# Main-v5_0.net
KiCad netlist of a schematic drawn in EAGLE
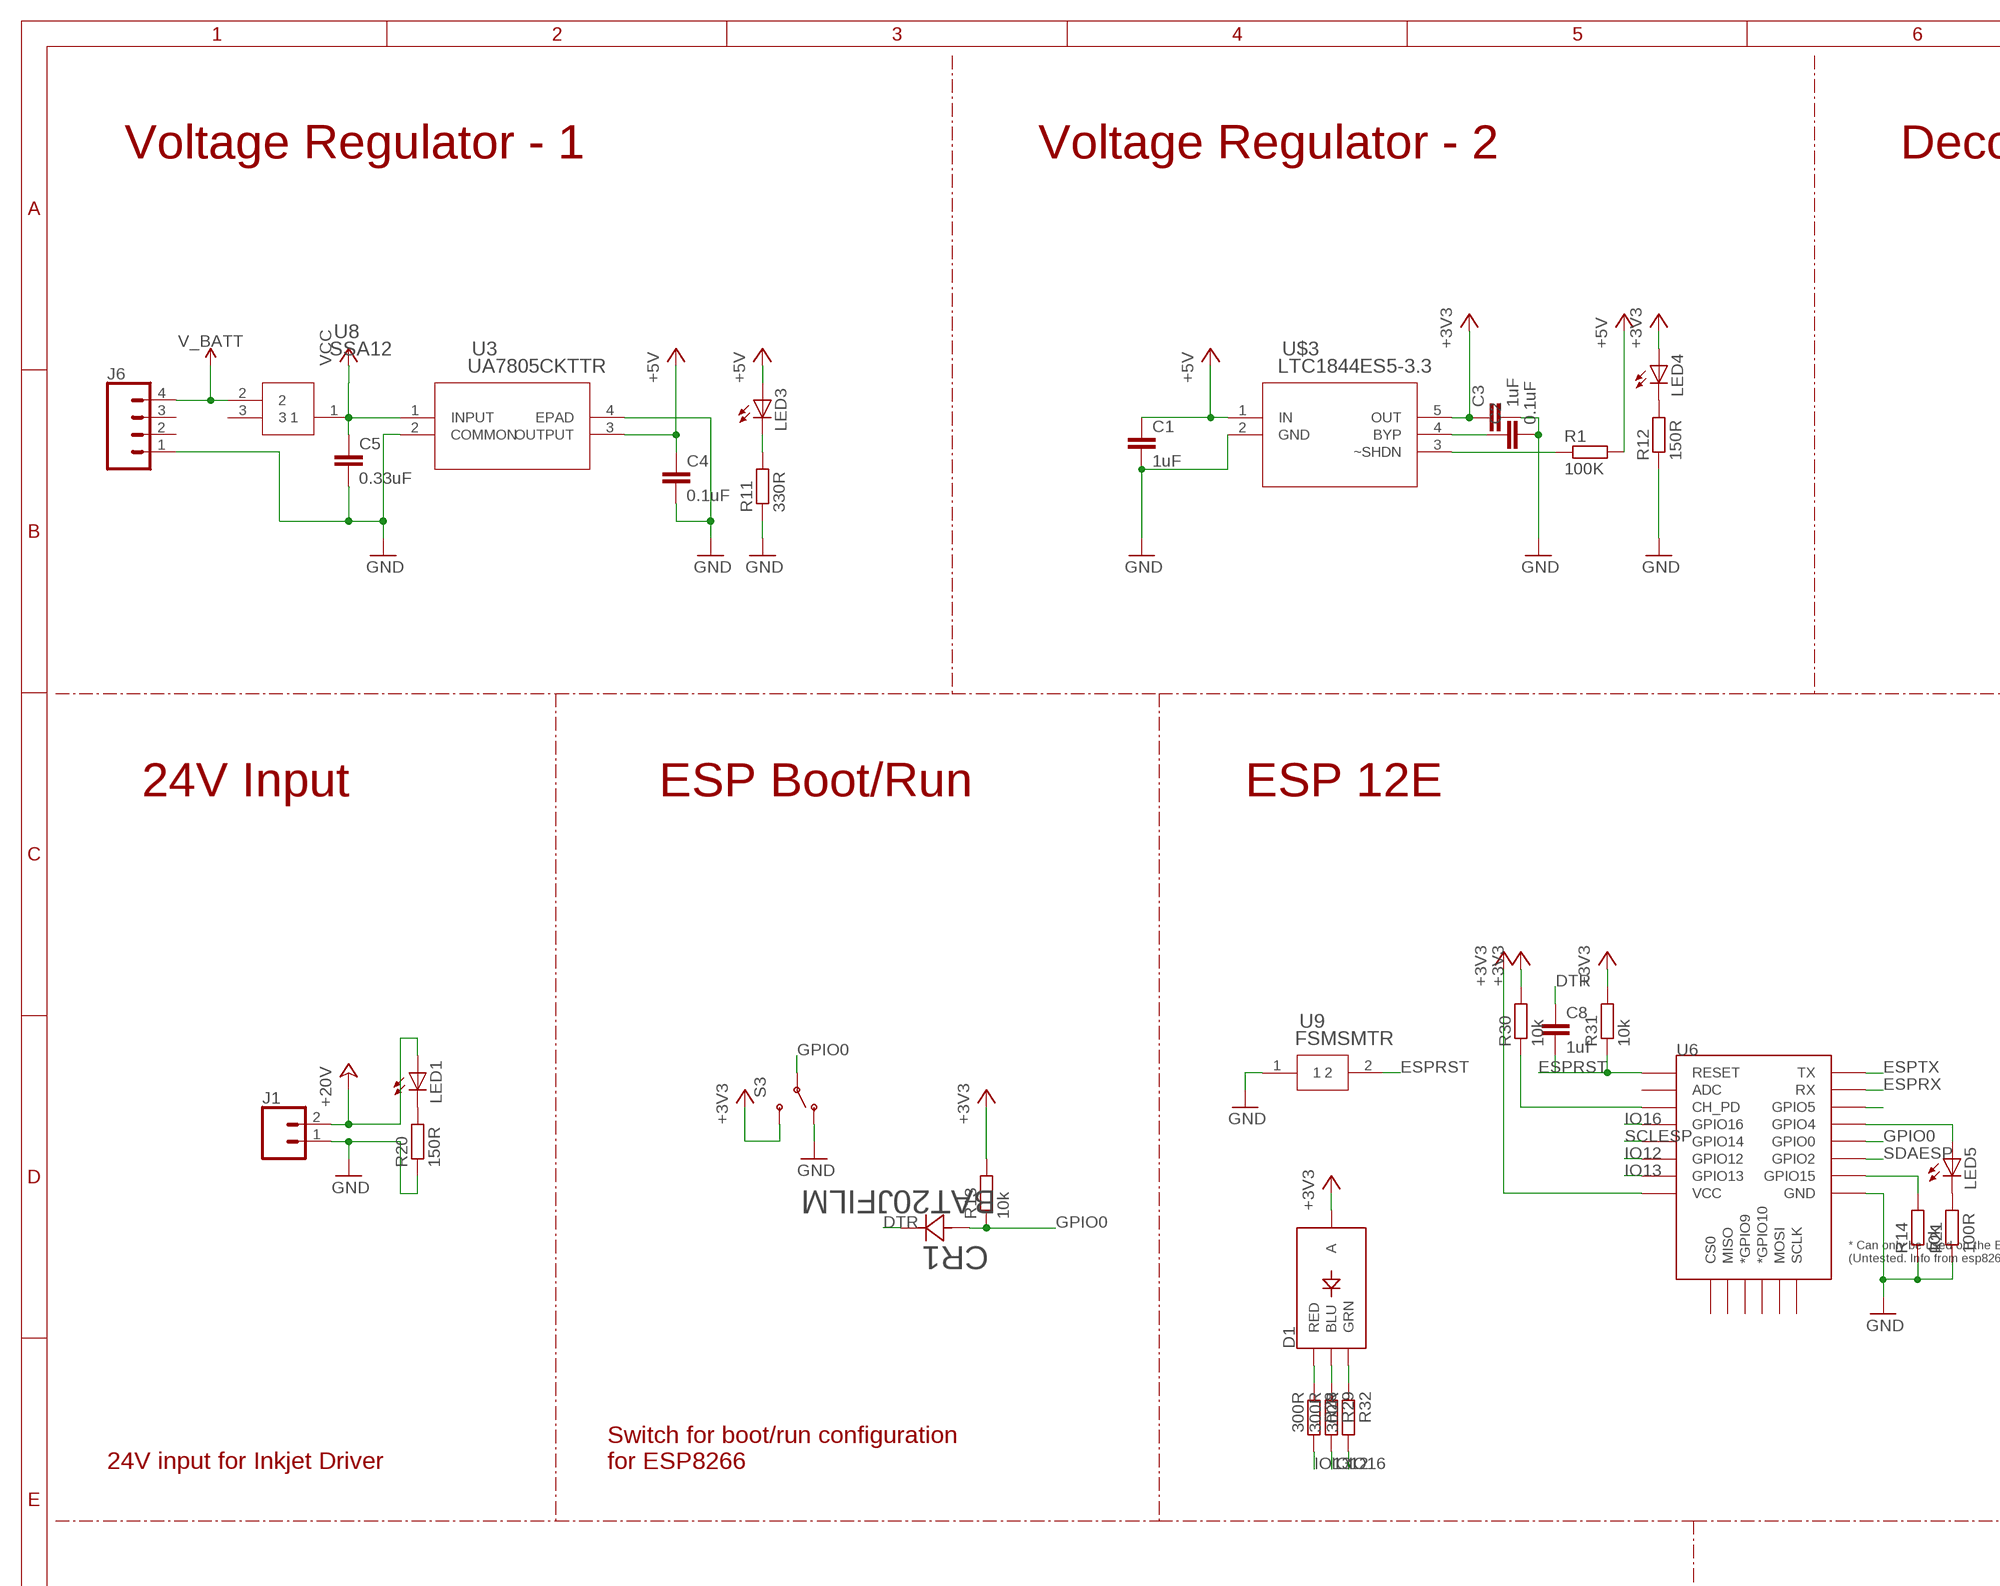
[diagram p0: schematic, sheet 1, part 1 of 3]
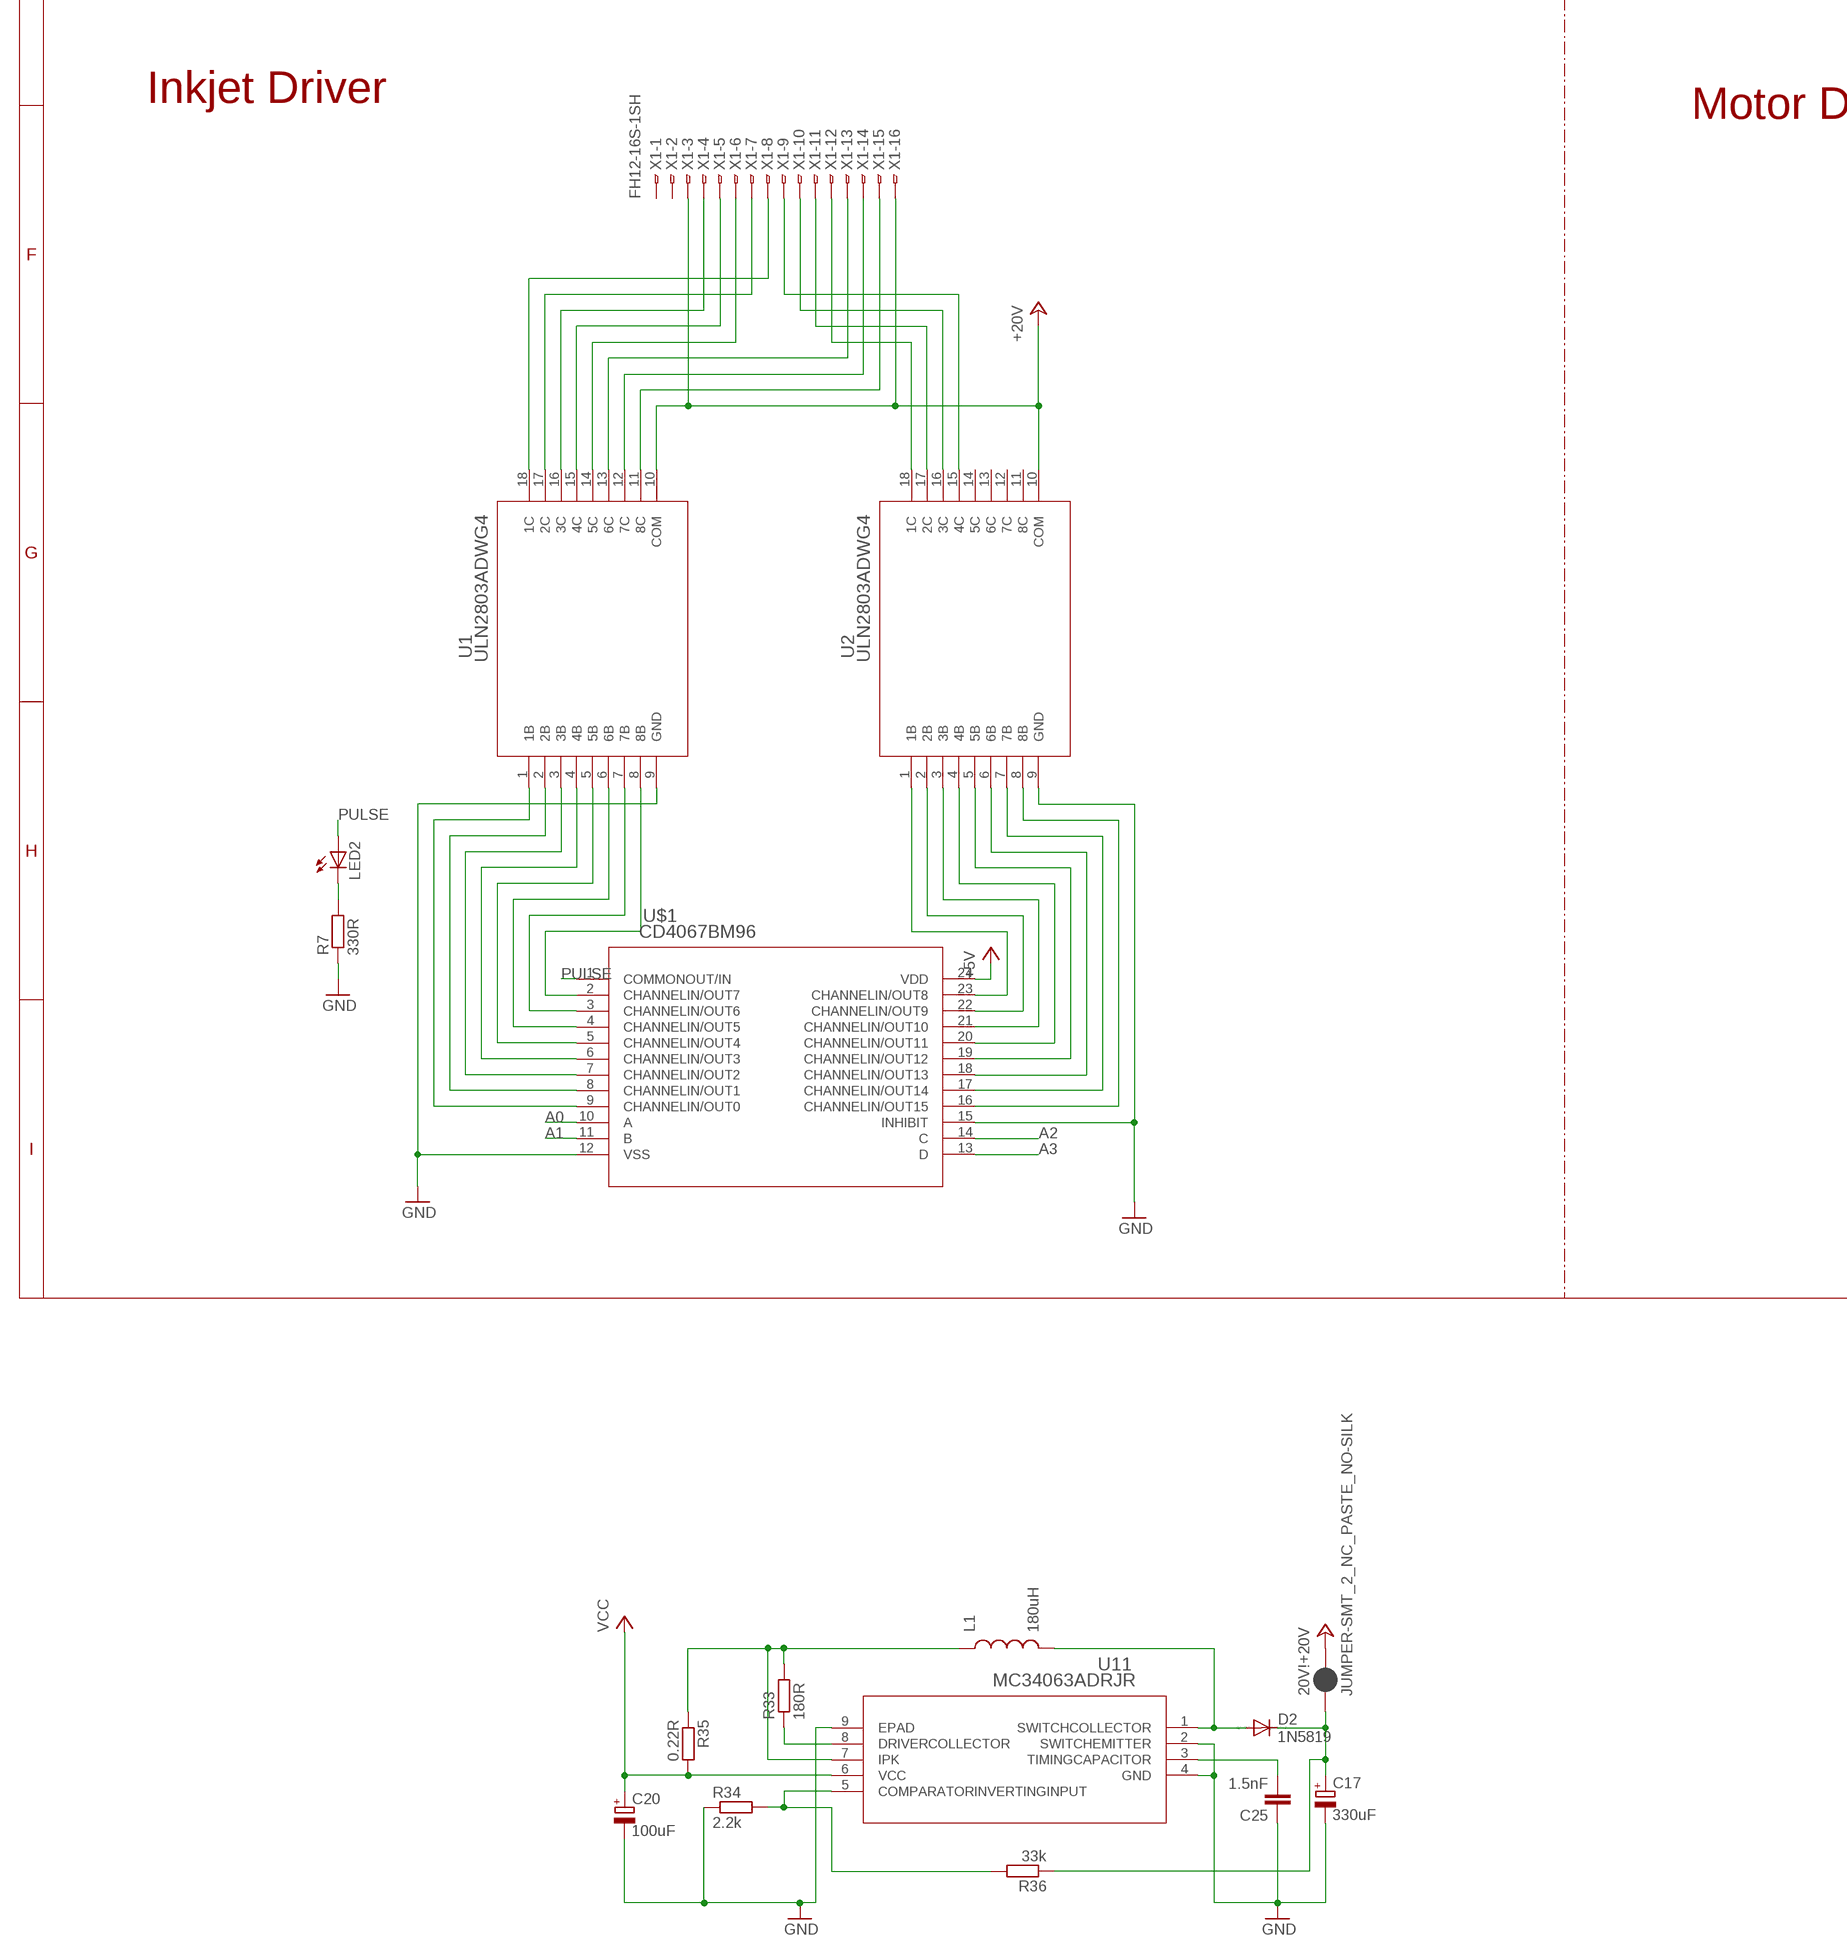
[diagram p1: schematic, sheet 1, part 2 of 3]
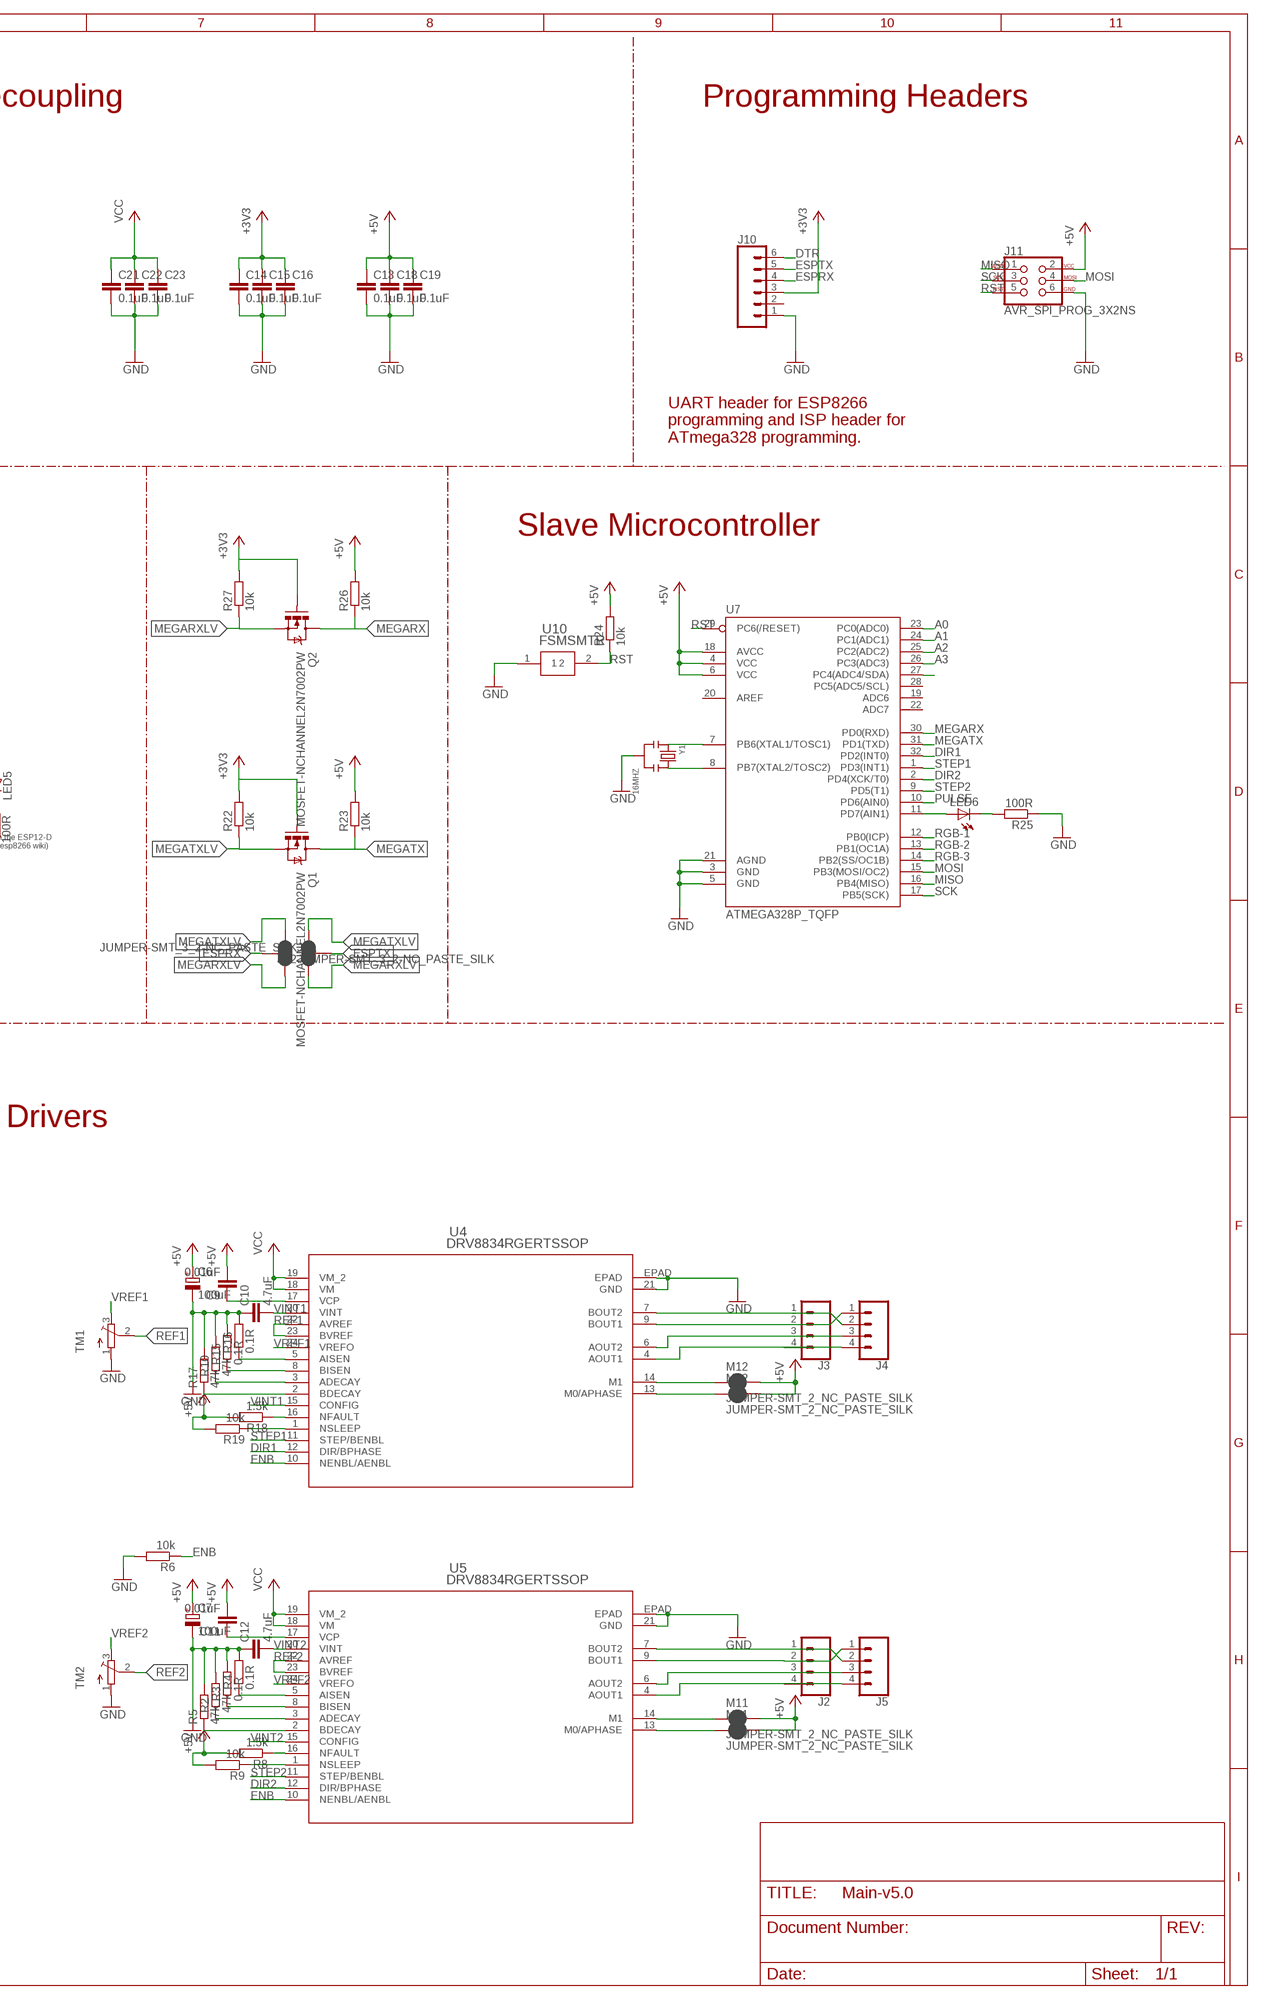
[diagram p2: schematic, sheet 1, part 3 of 3]

(export (version "E")
  (design (tool "Eeschema 10.0.6"))
  (components
    (comp (ref "20V!")
      (value "JUMPER-SMT_2_NC_PASTE_NO-SILK")
      (footprint "eagle-import:SMT-JUMPER_2_NC_PASTE_NO-SILK")
      (libsource (lib "eagle-import") (part "JUMPER-SMT_2_NC_PASTE_NO-SILK"))
    )
    (comp (ref "C1")
      (value "1uF")
      (footprint "eagle-import:C0603")
      (libsource (lib "eagle-import") (part "C-EUC0603"))
    )
    (comp (ref "C2")
      (value "0.1uF")
      (footprint "eagle-import:C0603")
      (libsource (lib "eagle-import") (part "C-EUC0603"))
    )
    (comp (ref "C3")
      (value "1uF")
      (footprint "eagle-import:C0603")
      (libsource (lib "eagle-import") (part "C-EUC0603"))
    )
    (comp (ref "C4")
      (value "0.1uF")
      (footprint "eagle-import:C0603")
      (libsource (lib "eagle-import") (part "C-EUC0603"))
    )
    (comp (ref "C5")
      (value "0.33uF")
      (footprint "eagle-import:C0603")
      (libsource (lib "eagle-import") (part "C-EUC0603"))
    )
    (comp (ref "C6")
      (value "100uF")
      (footprint "eagle-import:E5-5")
      (libsource (lib "eagle-import") (part "CPOL-EUE5-5"))
    )
    (comp (ref "C7")
      (value "100uF")
      (footprint "eagle-import:E5-5")
      (libsource (lib "eagle-import") (part "CPOL-EUE5-5"))
    )
    (comp (ref "C8")
      (value "1uf")
      (footprint "eagle-import:C0603")
      (libsource (lib "eagle-import") (part "resistor_348_C-EUC0603"))
    )
    (comp (ref "C9")
      (value "0.01uF")
      (footprint "eagle-import:C0603K")
      (libsource (lib "eagle-import") (part "resistor_348_C-EUC0603K"))
    )
    (comp (ref "C10")
      (value "4.7uF")
      (footprint "eagle-import:C0603K")
      (libsource (lib "eagle-import") (part "resistor_348_C-EUC0603K"))
    )
    (comp (ref "C11")
      (value "0.01uF")
      (footprint "eagle-import:C0603K")
      (libsource (lib "eagle-import") (part "resistor_348_C-EUC0603K"))
    )
    (comp (ref "C12")
      (value "4.7uF")
      (footprint "eagle-import:C0603K")
      (libsource (lib "eagle-import") (part "resistor_348_C-EUC0603K"))
    )
    (comp (ref "C13")
      (value "0.1uF")
      (footprint "eagle-import:C0603")
      (libsource (lib "eagle-import") (part "C-EUC0603"))
    )
    (comp (ref "C14")
      (value "0.1uF")
      (footprint "eagle-import:C0603")
      (libsource (lib "eagle-import") (part "C-EUC0603"))
    )
    (comp (ref "C15")
      (value "0.1uF")
      (footprint "eagle-import:C0603")
      (libsource (lib "eagle-import") (part "C-EUC0603"))
    )
    (comp (ref "C16")
      (value "0.1uF")
      (footprint "eagle-import:C0603")
      (libsource (lib "eagle-import") (part "C-EUC0603"))
    )
    (comp (ref "C17")
      (value "330uF")
      (footprint "eagle-import:153CLV-1010")
      (libsource (lib "eagle-import") (part "resistor_348_CPOL-EU153CLV-1010"))
    )
    (comp (ref "C18")
      (value "0.1uF")
      (footprint "eagle-import:C0603")
      (libsource (lib "eagle-import") (part "C-EUC0603"))
    )
    (comp (ref "C19")
      (value "0.1uF")
      (footprint "eagle-import:C0603")
      (libsource (lib "eagle-import") (part "C-EUC0603"))
    )
    (comp (ref "C20")
      (value "100uF")
      (footprint "eagle-import:SMC_C")
      (libsource (lib "eagle-import") (part "resistor_348_CPOL-EUSMCC"))
    )
    (comp (ref "C21")
      (value "0.1uF")
      (footprint "eagle-import:C0603")
      (libsource (lib "eagle-import") (part "C-EUC0603"))
    )
    (comp (ref "C22")
      (value "0.1uF")
      (footprint "eagle-import:C0603")
      (libsource (lib "eagle-import") (part "C-EUC0603"))
    )
    (comp (ref "C23")
      (value "0.1uF")
      (footprint "eagle-import:C0603")
      (libsource (lib "eagle-import") (part "C-EUC0603"))
    )
    (comp (ref "C25")
      (value "1.5nF")
      (footprint "eagle-import:C0603K")
      (libsource (lib "eagle-import") (part "resistor_348_C-EUC0603K"))
    )
    (comp (ref "CR1")
      (value "BAT20JFILM")
      (footprint "eagle-import:SOD-323")
      (libsource (lib "eagle-import") (part "BAT20JFILM"))
    )
    (comp (ref "D1")
      (value "LED-RGB-CASMD")
      (footprint "eagle-import:LED-TRICOLOR-SMD")
      (libsource (lib "eagle-import") (part "LED-RGB-CASMD"))
    )
    (comp (ref "D2")
      (value "1N5819")
      (footprint "eagle-import:SOD123")
      (libsource (lib "eagle-import") (part "1N5819"))
    )
    (comp (ref "J1")
      (value "CONN_02")
      (footprint "eagle-import:1X02")
      (libsource (lib "eagle-import") (part "CONN_02"))
    )
    (comp (ref "J2")
      (value "CONN_04")
      (footprint "eagle-import:1X04")
      (libsource (lib "eagle-import") (part "CONN_04"))
    )
    (comp (ref "J3")
      (value "CONN_04")
      (footprint "eagle-import:1X04")
      (libsource (lib "eagle-import") (part "CONN_04"))
    )
    (comp (ref "J4")
      (value "CONN_04")
      (footprint "eagle-import:1X04")
      (libsource (lib "eagle-import") (part "CONN_04"))
    )
    (comp (ref "J5")
      (value "CONN_04")
      (footprint "eagle-import:1X04")
      (libsource (lib "eagle-import") (part "CONN_04"))
    )
    (comp (ref "J6")
      (value "CONN_04")
      (footprint "eagle-import:1X04")
      (libsource (lib "eagle-import") (part "CONN_04"))
    )
    (comp (ref "J10")
      (value "CONN_06NO_SILK_NO_POP")
      (footprint "eagle-import:1X06_NO_SILK")
      (libsource (lib "eagle-import") (part "CONN_06NO_SILK_NO_POP"))
    )
    (comp (ref "J11")
      (value "AVR_SPI_PROG_3X2NS")
      (footprint "eagle-import:2X3-NS")
      (libsource (lib "eagle-import") (part "AVR_SPI_PROG_3X2NS"))
    )
    (comp (ref "JP1")
      (value "JUMPER-SMT_3_2-NC_PASTE_SILK")
      (footprint "eagle-import:SMT-JUMPER_3_2-NC_PASTE_SILK")
      (libsource (lib "eagle-import") (part "JUMPER-SMT_3_2-NC_PASTE_SILK"))
    )
    (comp (ref "JP2")
      (value "JUMPER-SMT_3_2-NC_PASTE_SILK")
      (footprint "eagle-import:SMT-JUMPER_3_2-NC_PASTE_SILK")
      (libsource (lib "eagle-import") (part "JUMPER-SMT_3_2-NC_PASTE_SILK"))
    )
    (comp (ref "L1")
      (value "180uH")
      (footprint "eagle-import:CR54")
      (libsource (lib "eagle-import") (part "INDUCTORCR54"))
    )
    (comp (ref "LED1")
      (value "LEDSML0603")
      (footprint "eagle-import:SML0603")
      (libsource (lib "eagle-import") (part "LEDSML0603"))
    )
    (comp (ref "LED2")
      (value "LEDSML0603")
      (footprint "eagle-import:SML0603")
      (libsource (lib "eagle-import") (part "LEDSML0603"))
    )
    (comp (ref "LED3")
      (value "LEDSML0603")
      (footprint "eagle-import:SML0603")
      (libsource (lib "eagle-import") (part "LEDSML0603"))
    )
    (comp (ref "LED4")
      (value "LEDSML0603")
      (footprint "eagle-import:SML0603")
      (libsource (lib "eagle-import") (part "LEDSML0603"))
    )
    (comp (ref "LED5")
      (value "LEDSML0603")
      (footprint "eagle-import:SML0603")
      (libsource (lib "eagle-import") (part "LEDSML0603"))
    )
    (comp (ref "LED6")
      (value "LEDSML0603")
      (footprint "eagle-import:SML0603")
      (libsource (lib "eagle-import") (part "LEDSML0603"))
    )
    (comp (ref "M01")
      (value "JUMPER-SMT_2_NC_PASTE_SILK")
      (footprint "eagle-import:SMT-JUMPER_2_NC_PASTE_SILK")
      (libsource (lib "eagle-import") (part "JUMPER-SMT_2_NC_PASTE_SILK"))
    )
    (comp (ref "M02")
      (value "JUMPER-SMT_2_NC_PASTE_SILK")
      (footprint "eagle-import:SMT-JUMPER_2_NC_PASTE_SILK")
      (libsource (lib "eagle-import") (part "JUMPER-SMT_2_NC_PASTE_SILK"))
    )
    (comp (ref "M11")
      (value "JUMPER-SMT_2_NC_PASTE_SILK")
      (footprint "eagle-import:SMT-JUMPER_2_NC_PASTE_SILK")
      (libsource (lib "eagle-import") (part "JUMPER-SMT_2_NC_PASTE_SILK"))
    )
    (comp (ref "M12")
      (value "JUMPER-SMT_2_NC_PASTE_SILK")
      (footprint "eagle-import:SMT-JUMPER_2_NC_PASTE_SILK")
      (libsource (lib "eagle-import") (part "JUMPER-SMT_2_NC_PASTE_SILK"))
    )
    (comp (ref "Q1")
      (value "MOSFET-NCHANNEL2N7002PW")
      (footprint "eagle-import:SOT323")
      (libsource (lib "eagle-import") (part "MOSFET-NCHANNEL2N7002PW"))
    )
    (comp (ref "Q2")
      (value "MOSFET-NCHANNEL2N7002PW")
      (footprint "eagle-import:SOT323")
      (libsource (lib "eagle-import") (part "MOSFET-NCHANNEL2N7002PW"))
    )
    (comp (ref "R1")
      (value "100K")
      (footprint "eagle-import:R0603")
      (libsource (lib "eagle-import") (part "R-EU_R0603"))
    )
    (comp (ref "R2")
      (value "47k")
      (footprint "eagle-import:R0402")
      (libsource (lib "eagle-import") (part "resistor_348_R-EU_R0402"))
    )
    (comp (ref "R3")
      (value "0.1R")
      (footprint "eagle-import:R0402")
      (libsource (lib "eagle-import") (part "resistor_348_R-EU_R0402"))
    )
    (comp (ref "R4")
      (value "0.1R")
      (footprint "eagle-import:R0402")
      (libsource (lib "eagle-import") (part "resistor_348_R-EU_R0402"))
    )
    (comp (ref "R5")
      (value "47k")
      (footprint "eagle-import:R0402")
      (libsource (lib "eagle-import") (part "resistor_348_R-EU_R0402"))
    )
    (comp (ref "R6")
      (value "10k")
      (footprint "eagle-import:R0402")
      (libsource (lib "eagle-import") (part "resistor_348_R-EU_R0402"))
    )
    (comp (ref "R7")
      (value "330R")
      (footprint "eagle-import:R0603")
      (libsource (lib "eagle-import") (part "R-EU_R0603"))
    )
    (comp (ref "R8")
      (value "1.5k")
      (footprint "eagle-import:R0402")
      (libsource (lib "eagle-import") (part "resistor_348_R-EU_R0402"))
    )
    (comp (ref "R9")
      (value "10k")
      (footprint "eagle-import:R0402")
      (libsource (lib "eagle-import") (part "resistor_348_R-EU_R0402"))
    )
    (comp (ref "R10")
      (value "47k")
      (footprint "eagle-import:R0402")
      (libsource (lib "eagle-import") (part "resistor_348_R-EU_R0402"))
    )
    (comp (ref "R11")
      (value "330R")
      (footprint "eagle-import:R0603")
      (libsource (lib "eagle-import") (part "R-EU_R0603"))
    )
    (comp (ref "R12")
      (value "150R")
      (footprint "eagle-import:R0603")
      (libsource (lib "eagle-import") (part "R-EU_R0603"))
    )
    (comp (ref "R13")
      (value "10k")
      (footprint "eagle-import:R0603")
      (libsource (lib "eagle-import") (part "R-EU_R0603"))
    )
    (comp (ref "R14")
      (value "10k")
      (footprint "eagle-import:R0603")
      (libsource (lib "eagle-import") (part "R-EU_R0603"))
    )
    (comp (ref "R15")
      (value "0.1R")
      (footprint "eagle-import:R0402")
      (libsource (lib "eagle-import") (part "resistor_348_R-EU_R0402"))
    )
    (comp (ref "R16")
      (value "0.1R")
      (footprint "eagle-import:R0402")
      (libsource (lib "eagle-import") (part "resistor_348_R-EU_R0402"))
    )
    (comp (ref "R17")
      (value "47k")
      (footprint "eagle-import:R0402")
      (libsource (lib "eagle-import") (part "resistor_348_R-EU_R0402"))
    )
    (comp (ref "R18")
      (value "1.5k")
      (footprint "eagle-import:R0402")
      (libsource (lib "eagle-import") (part "resistor_348_R-EU_R0402"))
    )
    (comp (ref "R19")
      (value "10k")
      (footprint "eagle-import:R0402")
      (libsource (lib "eagle-import") (part "resistor_348_R-EU_R0402"))
    )
    (comp (ref "R20")
      (value "150R")
      (footprint "eagle-import:R0603")
      (libsource (lib "eagle-import") (part "R-EU_R0603"))
    )
    (comp (ref "R21")
      (value "100R")
      (footprint "eagle-import:R0603")
      (libsource (lib "eagle-import") (part "R-EU_R0603"))
    )
    (comp (ref "R22")
      (value "10k")
      (footprint "eagle-import:R0603")
      (libsource (lib "eagle-import") (part "R-EU_R0603"))
    )
    (comp (ref "R23")
      (value "10k")
      (footprint "eagle-import:R0603")
      (libsource (lib "eagle-import") (part "R-EU_R0603"))
    )
    (comp (ref "R24")
      (value "10k")
      (footprint "eagle-import:R0603")
      (libsource (lib "eagle-import") (part "R-EU_R0603"))
    )
    (comp (ref "R25")
      (value "100R")
      (footprint "eagle-import:R0603")
      (libsource (lib "eagle-import") (part "R-EU_R0603"))
    )
    (comp (ref "R26")
      (value "10k")
      (footprint "eagle-import:R0603")
      (libsource (lib "eagle-import") (part "R-EU_R0603"))
    )
    (comp (ref "R27")
      (value "10k")
      (footprint "eagle-import:R0603")
      (libsource (lib "eagle-import") (part "R-EU_R0603"))
    )
    (comp (ref "R28")
      (value "300R")
      (footprint "eagle-import:R0603")
      (libsource (lib "eagle-import") (part "R-EU_R0603"))
    )
    (comp (ref "R29")
      (value "300R")
      (footprint "eagle-import:R0603")
      (libsource (lib "eagle-import") (part "R-EU_R0603"))
    )
    (comp (ref "R30")
      (value "10k")
      (footprint "eagle-import:R0603")
      (libsource (lib "eagle-import") (part "R-EU_R0603"))
    )
    (comp (ref "R31")
      (value "10k")
      (footprint "eagle-import:R0603")
      (libsource (lib "eagle-import") (part "R-EU_R0603"))
    )
    (comp (ref "R32")
      (value "300R")
      (footprint "eagle-import:R0603")
      (libsource (lib "eagle-import") (part "R-EU_R0603"))
    )
    (comp (ref "R33")
      (value "180R")
      (footprint "eagle-import:R0603")
      (libsource (lib "eagle-import") (part "R-EU_R0603"))
    )
    (comp (ref "R34")
      (value "2.2k")
      (footprint "eagle-import:R0603")
      (libsource (lib "eagle-import") (part "R-EU_R0603"))
    )
    (comp (ref "R35")
      (value "0.22R")
      (footprint "eagle-import:R0603")
      (libsource (lib "eagle-import") (part "R-EU_R0603"))
    )
    (comp (ref "R36")
      (value "33k")
      (footprint "eagle-import:R0603")
      (libsource (lib "eagle-import") (part "R-EU_R0603"))
    )
    (comp (ref "S3")
      (value "SWITCH-SPDT-SMD-A")
      (footprint "eagle-import:SWITCH-SPST-SMD-A")
      (libsource (lib "eagle-import") (part "SWITCH-SPDT-SMD-A"))
    )
    (comp (ref "TM1")
      (value "TRIMPOTTC33X")
      (footprint "eagle-import:TC33X")
      (libsource (lib "eagle-import") (part "TRIMPOTTC33X"))
    )
    (comp (ref "TM2")
      (value "TRIMPOTTC33X")
      (footprint "eagle-import:TC33X")
      (libsource (lib "eagle-import") (part "TRIMPOTTC33X"))
    )
    (comp (ref "U$1")
      (value "CD4067BM96")
      (footprint "eagle-import:DW24")
      (fields (field (name "MANUFACTURER_PART_NUMBER") "CD4067B_DW_24"))
      (libsource (lib "eagle-import") (part "CD4067BM96"))
    )
    (comp (ref "U$3")
      (value "LTC1844ES5-3.3")
      (footprint "eagle-import:TSOT-23_S5")
      (libsource (lib "eagle-import") (part "LTC1844ES5-3.3"))
    )
    (comp (ref "U1")
      (value "ULN2803ADWG4")
      (footprint "eagle-import:DW18")
      (libsource (lib "eagle-import") (part "ULN2803ADWG4"))
    )
    (comp (ref "U2")
      (value "ULN2803ADWG4")
      (footprint "eagle-import:DW18")
      (libsource (lib "eagle-import") (part "ULN2803ADWG4"))
    )
    (comp (ref "U3")
      (value "UA7805CKTTR")
      (footprint "eagle-import:KTT3_6P22X6P6")
      (libsource (lib "eagle-import") (part "UA7805CKTTR"))
    )
    (comp (ref "U4")
      (value "DRV8834RGERTSSOP")
      (footprint "eagle-import:PWP_24")
      (libsource (lib "eagle-import") (part "DRV8834RGERTSSOP"))
    )
    (comp (ref "U5")
      (value "DRV8834RGERTSSOP")
      (footprint "eagle-import:PWP_24")
      (libsource (lib "eagle-import") (part "DRV8834RGERTSSOP"))
    )
    (comp (ref "U6")
      (value "ESP12ESMD")
      (footprint "eagle-import:ESP12E-SMD")
      (libsource (lib "eagle-import") (part "ESP12ESMD"))
    )
    (comp (ref "U7")
      (value "ATMEGA328P_TQFP")
      (footprint "eagle-import:TQFP32-08")
      (libsource (lib "eagle-import") (part "ATMEGA328P_TQFP"))
    )
    (comp (ref "U8")
      (value "SSA12")
      (footprint "eagle-import:SWSIP3-P98")
      (libsource (lib "eagle-import") (part "SSA12"))
    )
    (comp (ref "U9")
      (value "FSMSMTR")
      (footprint "eagle-import:SWITCH_FSMSMTR")
      (libsource (lib "eagle-import") (part "FSMSMTR"))
    )
    (comp (ref "U10")
      (value "FSMSMTR")
      (footprint "eagle-import:SWITCH_FSMSMTR")
      (libsource (lib "eagle-import") (part "FSMSMTR"))
    )
    (comp (ref "U11")
      (value "MC34063ADRJR")
      (footprint "eagle-import:DRJ8_2P2X3")
      (libsource (lib "eagle-import") (part "MC34063ADRJR"))
    )
    (comp (ref "X1")
      (value "FH12-16S-1SH")
      (footprint "eagle-import:FH12-16S-1SH")
      (libsource (lib "eagle-import") (part "FH12-16S-1SH"))
    )
    (comp (ref "Y1")
      (value "16MHZ")
      (footprint "eagle-import:X3-SMD-3.6X1.3X0.8MM")
      (fields (field (name "MPN") "CSTCE16M0V53-R0"))
      (libsource (lib "eagle-import") (part "SMD-RESONATOR-16MHZ-15PF-0.5%-40R(3P-3.2X1.3MM)"))
    )
  )
  (nets
    (net (code "1") (name "+3V3") (class "Default")
      (node (ref "C14") (pin "1") (pinfunction "1_1") (pintype "passive"))
      (node (ref "C15") (pin "1") (pinfunction "1_1") (pintype "passive"))
      (node (ref "C16") (pin "1") (pinfunction "1_1") (pintype "passive"))
      (node (ref "C3") (pin "1") (pinfunction "1_1") (pintype "passive"))
      (node (ref "D1") (pin "A") (pinfunction "A_A") (pintype "bidirectional"))
      (node (ref "J10") (pin "3") (pinfunction "3_3") (pintype "passive"))
      (node (ref "LED4") (pin "A") (pinfunction "A_A") (pintype "passive"))
      (node (ref "Q1") (pin "1") (pinfunction "G_1") (pintype "passive"))
      (node (ref "Q2") (pin "1") (pinfunction "G_1") (pintype "passive"))
      (node (ref "R13") (pin "2") (pinfunction "2_2") (pintype "passive"))
      (node (ref "R22") (pin "2") (pinfunction "2_2") (pintype "passive"))
      (node (ref "R27") (pin "2") (pinfunction "2_2") (pintype "passive"))
      (node (ref "R30") (pin "2") (pinfunction "2_2") (pintype "passive"))
      (node (ref "R31") (pin "2") (pinfunction "2_2") (pintype "passive"))
      (node (ref "S3") (pin "3") (pinfunction "S_3") (pintype "passive"))
      (node (ref "U$3") (pin "5") (pinfunction "OUT_5") (pintype "passive"))
      (node (ref "U6") (pin "VCC") (pinfunction "VCC_VCC") (pintype "bidirectional"))
    )
    (net (code "2") (name "+5V") (class "Default")
      (node (ref "C1") (pin "1") (pinfunction "1_1") (pintype "passive"))
      (node (ref "C11") (pin "2") (pinfunction "2_2") (pintype "passive"))
      (node (ref "C13") (pin "1") (pinfunction "1_1") (pintype "passive"))
      (node (ref "C18") (pin "1") (pinfunction "1_1") (pintype "passive"))
      (node (ref "C19") (pin "1") (pinfunction "1_1") (pintype "passive"))
      (node (ref "C4") (pin "1") (pinfunction "1_1") (pintype "passive"))
      (node (ref "C6") (pin "+") (pinfunction "+_+") (pintype "passive"))
      (node (ref "C7") (pin "+") (pinfunction "+_+") (pintype "passive"))
      (node (ref "C9") (pin "2") (pinfunction "2_2") (pintype "passive"))
      (node (ref "J11") (pin "2") (pinfunction "2_2") (pintype "passive"))
      (node (ref "LED3") (pin "A") (pinfunction "A_A") (pintype "passive"))
      (node (ref "M01") (pin "2") (pinfunction "2_2") (pintype "passive"))
      (node (ref "M02") (pin "2") (pinfunction "2_2") (pintype "passive"))
      (node (ref "M11") (pin "2") (pinfunction "2_2") (pintype "passive"))
      (node (ref "M12") (pin "2") (pinfunction "2_2") (pintype "passive"))
      (node (ref "R1") (pin "2") (pinfunction "2_2") (pintype "passive"))
      (node (ref "R18") (pin "2") (pinfunction "2_2") (pintype "passive"))
      (node (ref "R19") (pin "2") (pinfunction "2_2") (pintype "passive"))
      (node (ref "R23") (pin "2") (pinfunction "2_2") (pintype "passive"))
      (node (ref "R24") (pin "2") (pinfunction "2_2") (pintype "passive"))
      (node (ref "R26") (pin "2") (pinfunction "2_2") (pintype "passive"))
      (node (ref "R8") (pin "2") (pinfunction "2_2") (pintype "passive"))
      (node (ref "R9") (pin "2") (pinfunction "2_2") (pintype "passive"))
      (node (ref "U$1") (pin "24") (pinfunction "VDD_24") (pintype "power_in"))
      (node (ref "U$3") (pin "1") (pinfunction "IN_1") (pintype "passive"))
      (node (ref "U3") (pin "3") (pinfunction "OUTPUT_3") (pintype "output"))
      (node (ref "U7") (pin "18") (pinfunction "AVCC_18") (pintype "bidirectional"))
      (node (ref "U7") (pin "4") (pinfunction "VCC_4") (pintype "bidirectional"))
      (node (ref "U7") (pin "6") (pinfunction "VCC_6") (pintype "bidirectional"))
    )
    (net (code "3") (name "+20V") (class "Default")
      (node (ref "20V!") (pin "2") (pinfunction "2_2") (pintype "passive"))
      (node (ref "J1") (pin "2") (pinfunction "2_2") (pintype "passive"))
      (node (ref "LED1") (pin "A") (pinfunction "A_A") (pintype "passive"))
      (node (ref "U1") (pin "10") (pinfunction "COM_10") (pintype "passive"))
      (node (ref "U2") (pin "10") (pinfunction "COM_10") (pintype "passive"))
      (node (ref "X1") (pin "16") (pinfunction "1_16") (pintype "passive"))
      (node (ref "X1") (pin "3") (pinfunction "1_3") (pintype "passive"))
    )
    (net (code "4") (name "/A0") (class "Default")
      (node (ref "U$1") (pin "10") (pinfunction "A_10") (pintype "passive"))
      (node (ref "U7") (pin "23") (pinfunction "PC0(ADC0)_23") (pintype "bidirectional"))
    )
    (net (code "5") (name "/A1") (class "Default")
      (node (ref "U$1") (pin "11") (pinfunction "B_11") (pintype "passive"))
      (node (ref "U7") (pin "24") (pinfunction "PC1(ADC1)_24") (pintype "bidirectional"))
    )
    (net (code "6") (name "/A2") (class "Default")
      (node (ref "U$1") (pin "14") (pinfunction "C_14") (pintype "passive"))
      (node (ref "U7") (pin "25") (pinfunction "PC2(ADC2)_25") (pintype "bidirectional"))
    )
    (net (code "7") (name "/A3") (class "Default")
      (node (ref "U$1") (pin "13") (pinfunction "D_13") (pintype "passive"))
      (node (ref "U7") (pin "26") (pinfunction "PC3(ADC3)_26") (pintype "bidirectional"))
    )
    (net (code "8") (name "/DIR1") (class "Default")
      (node (ref "U4") (pin "12") (pinfunction "DIR/BPHASE_12") (pintype "input"))
      (node (ref "U7") (pin "32") (pinfunction "PD2(INT0)_32") (pintype "bidirectional"))
    )
    (net (code "9") (name "/DIR2") (class "Default")
      (node (ref "U5") (pin "12") (pinfunction "DIR/BPHASE_12") (pintype "input"))
      (node (ref "U7") (pin "2") (pinfunction "PD4(XCK/T0)_2") (pintype "bidirectional"))
    )
    (net (code "10") (name "/DTR") (class "Default")
      (node (ref "C8") (pin "1") (pinfunction "1_1") (pintype "passive"))
      (node (ref "CR1") (pin "1") (pinfunction "11_1") (pintype "passive"))
      (node (ref "J10") (pin "6") (pinfunction "6_6") (pintype "passive"))
    )
    (net (code "11") (name "/ENB") (class "Default")
      (node (ref "R6") (pin "1") (pinfunction "1_1") (pintype "passive"))
      (node (ref "U4") (pin "10") (pinfunction "NENBL/AENBL_10") (pintype "input"))
      (node (ref "U5") (pin "10") (pinfunction "NENBL/AENBL_10") (pintype "input"))
    )
    (net (code "12") (name "/ESPRST") (class "Default")
      (node (ref "C8") (pin "2") (pinfunction "2_2") (pintype "passive"))
      (node (ref "R31") (pin "1") (pinfunction "1_1") (pintype "passive"))
      (node (ref "U6") (pin "RESET") (pinfunction "RESET_RESET") (pintype "bidirectional"))
      (node (ref "U9") (pin "2") (pinfunction "2_2") (pintype "passive"))
    )
    (net (code "13") (name "/GPIO0") (class "Default")
      (node (ref "CR1") (pin "2") (pinfunction "22_2") (pintype "passive"))
      (node (ref "R13") (pin "1") (pinfunction "1_1") (pintype "passive"))
      (node (ref "S3") (pin "2") (pinfunction "P_2") (pintype "passive"))
      (node (ref "U6") (pin "GPIO0") (pinfunction "GPIO0_GPIO0") (pintype "bidirectional"))
    )
    (net (code "14") (name "/IO12") (class "Default")
      (node (ref "R29") (pin "2") (pinfunction "2_2") (pintype "passive"))
      (node (ref "U6") (pin "GPIO12") (pinfunction "GPIO12_GPIO12") (pintype "bidirectional"))
    )
    (net (code "15") (name "/IO13") (class "Default")
      (node (ref "R28") (pin "2") (pinfunction "2_2") (pintype "passive"))
      (node (ref "U6") (pin "GPIO13") (pinfunction "GPIO13_GPIO13") (pintype "bidirectional"))
    )
    (net (code "16") (name "/IO16") (class "Default")
      (node (ref "R32") (pin "2") (pinfunction "2_2") (pintype "passive"))
      (node (ref "U6") (pin "GPIO16") (pinfunction "GPIO16_GPIO16") (pintype "bidirectional"))
    )
    (net (code "17") (name "/MISO") (class "Default")
      (node (ref "J11") (pin "1") (pinfunction "1_1") (pintype "passive"))
      (node (ref "U7") (pin "16") (pinfunction "PB4(MISO)_16") (pintype "bidirectional"))
    )
    (net (code "18") (name "/MOSI") (class "Default")
      (node (ref "J11") (pin "4") (pinfunction "4_4") (pintype "passive"))
      (node (ref "U7") (pin "15") (pinfunction "PB3(MOSI/OC2)_15") (pintype "bidirectional"))
    )
    (net (code "19") (name "/PULSE") (class "Default")
      (node (ref "LED2") (pin "A") (pinfunction "A_A") (pintype "passive"))
      (node (ref "U$1") (pin "1") (pinfunction "COMMONOUT/IN_1") (pintype "bidirectional"))
      (node (ref "U7") (pin "10") (pinfunction "PD6(AIN0)_10") (pintype "bidirectional"))
    )
    (net (code "20") (name "/RGB-1") (class "Default")
      (node (ref "U7") (pin "12") (pinfunction "PB0(ICP)_12") (pintype "bidirectional"))
    )
    (net (code "21") (name "/RGB-2") (class "Default")
      (node (ref "U7") (pin "13") (pinfunction "PB1(OC1A)_13") (pintype "bidirectional"))
    )
    (net (code "22") (name "/RGB-3") (class "Default")
      (node (ref "U7") (pin "14") (pinfunction "PB2(SS/OC1B)_14") (pintype "bidirectional"))
    )
    (net (code "23") (name "/RST") (class "Default")
      (node (ref "J11") (pin "5") (pinfunction "5_5") (pintype "passive"))
      (node (ref "R24") (pin "1") (pinfunction "1_1") (pintype "passive"))
      (node (ref "U10") (pin "2") (pinfunction "2_2") (pintype "passive"))
      (node (ref "U7") (pin "29") (pinfunction "PC6(/RESET)_29") (pintype "bidirectional"))
    )
    (net (code "24") (name "/SCK") (class "Default")
      (node (ref "J11") (pin "3") (pinfunction "3_3") (pintype "passive"))
      (node (ref "U7") (pin "17") (pinfunction "PB5(SCK)_17") (pintype "bidirectional"))
    )
    (net (code "25") (name "/SCLESP") (class "Default")
      (node (ref "U6") (pin "GPIO14") (pinfunction "GPIO14_GPIO14") (pintype "bidirectional"))
    )
    (net (code "26") (name "/SDAESP") (class "Default")
      (node (ref "U6") (pin "GPIO2") (pinfunction "GPIO2_GPIO2") (pintype "bidirectional"))
    )
    (net (code "27") (name "/STEP1") (class "Default")
      (node (ref "U4") (pin "11") (pinfunction "STEP/BENBL_11") (pintype "input"))
      (node (ref "U7") (pin "1") (pinfunction "PD3(INT1)_1") (pintype "bidirectional"))
    )
    (net (code "28") (name "/STEP2") (class "Default")
      (node (ref "U5") (pin "11") (pinfunction "STEP/BENBL_11") (pintype "input"))
      (node (ref "U7") (pin "9") (pinfunction "PD5(T1)_9") (pintype "bidirectional"))
    )
    (net (code "29") (name "/VINT1") (class "Default")
      (node (ref "C10") (pin "2") (pinfunction "2_2") (pintype "passive"))
      (node (ref "U4") (pin "15") (pinfunction "CONFIG_15") (pintype "input"))
      (node (ref "U4") (pin "20") (pinfunction "VINT_20") (pintype "passive"))
    )
    (net (code "30") (name "/VINT2") (class "Default")
      (node (ref "C12") (pin "2") (pinfunction "2_2") (pintype "passive"))
      (node (ref "U5") (pin "15") (pinfunction "CONFIG_15") (pintype "input"))
      (node (ref "U5") (pin "20") (pinfunction "VINT_20") (pintype "passive"))
    )
    (net (code "31") (name "/VREF1") (class "Default")
      (node (ref "TM1") (pin "3") (pinfunction "E_3") (pintype "passive"))
      (node (ref "U4") (pin "24") (pinfunction "VREFO_24") (pintype "output"))
    )
    (net (code "32") (name "/VREF2") (class "Default")
      (node (ref "TM2") (pin "3") (pinfunction "E_3") (pintype "passive"))
      (node (ref "U5") (pin "24") (pinfunction "VREFO_24") (pintype "output"))
    )
    (net (code "33") (name "ESPRX") (class "Default")
      (node (ref "J10") (pin "4") (pinfunction "4_4") (pintype "passive"))
      (node (ref "JP1") (pin "2") (pinfunction "2_2") (pintype "passive"))
      (node (ref "U6") (pin "RXD0") (pinfunction "RX_RXD0") (pintype "bidirectional"))
    )
    (net (code "34") (name "ESPTX") (class "Default")
      (node (ref "J10") (pin "5") (pinfunction "5_5") (pintype "passive"))
      (node (ref "JP2") (pin "2") (pinfunction "2_2") (pintype "passive"))
      (node (ref "U6") (pin "TXD0") (pinfunction "TX_TXD0") (pintype "bidirectional"))
    )
    (net (code "35") (name "GND") (class "Default")
      (node (ref "C1") (pin "2") (pinfunction "2_2") (pintype "passive"))
      (node (ref "C10") (pin "1") (pinfunction "1_1") (pintype "passive"))
      (node (ref "C12") (pin "1") (pinfunction "1_1") (pintype "passive"))
      (node (ref "C13") (pin "2") (pinfunction "2_2") (pintype "passive"))
      (node (ref "C14") (pin "2") (pinfunction "2_2") (pintype "passive"))
      (node (ref "C15") (pin "2") (pinfunction "2_2") (pintype "passive"))
      (node (ref "C16") (pin "2") (pinfunction "2_2") (pintype "passive"))
      (node (ref "C17") (pin "-") (pinfunction "-_-") (pintype "passive"))
      (node (ref "C18") (pin "2") (pinfunction "2_2") (pintype "passive"))
      (node (ref "C19") (pin "2") (pinfunction "2_2") (pintype "passive"))
      (node (ref "C2") (pin "2") (pinfunction "2_2") (pintype "passive"))
      (node (ref "C20") (pin "-") (pinfunction "-_-") (pintype "passive"))
      (node (ref "C21") (pin "2") (pinfunction "2_2") (pintype "passive"))
      (node (ref "C22") (pin "2") (pinfunction "2_2") (pintype "passive"))
      (node (ref "C23") (pin "2") (pinfunction "2_2") (pintype "passive"))
      (node (ref "C25") (pin "1") (pinfunction "1_1") (pintype "passive"))
      (node (ref "C3") (pin "2") (pinfunction "2_2") (pintype "passive"))
      (node (ref "C4") (pin "2") (pinfunction "2_2") (pintype "passive"))
      (node (ref "C5") (pin "2") (pinfunction "2_2") (pintype "passive"))
      (node (ref "C6") (pin "-") (pinfunction "-_-") (pintype "passive"))
      (node (ref "C7") (pin "-") (pinfunction "-_-") (pintype "passive"))
      (node (ref "J1") (pin "1") (pinfunction "1_1") (pintype "passive"))
      (node (ref "J10") (pin "1") (pinfunction "1_1") (pintype "passive"))
      (node (ref "J11") (pin "6") (pinfunction "6_6") (pintype "passive"))
      (node (ref "J6") (pin "1") (pinfunction "1_1") (pintype "passive"))
      (node (ref "R10") (pin "2") (pinfunction "2_2") (pintype "passive"))
      (node (ref "R11") (pin "1") (pinfunction "1_1") (pintype "passive"))
      (node (ref "R12") (pin "1") (pinfunction "1_1") (pintype "passive"))
      (node (ref "R14") (pin "1") (pinfunction "1_1") (pintype "passive"))
      (node (ref "R15") (pin "2") (pinfunction "2_2") (pintype "passive"))
      (node (ref "R16") (pin "2") (pinfunction "2_2") (pintype "passive"))
      (node (ref "R17") (pin "2") (pinfunction "2_2") (pintype "passive"))
      (node (ref "R2") (pin "2") (pinfunction "2_2") (pintype "passive"))
      (node (ref "R20") (pin "1") (pinfunction "1_1") (pintype "passive"))
      (node (ref "R21") (pin "1") (pinfunction "1_1") (pintype "passive"))
      (node (ref "R25") (pin "1") (pinfunction "1_1") (pintype "passive"))
      (node (ref "R3") (pin "2") (pinfunction "2_2") (pintype "passive"))
      (node (ref "R34") (pin "1") (pinfunction "1_1") (pintype "passive"))
      (node (ref "R4") (pin "2") (pinfunction "2_2") (pintype "passive"))
      (node (ref "R5") (pin "2") (pinfunction "2_2") (pintype "passive"))
      (node (ref "R6") (pin "2") (pinfunction "2_2") (pintype "passive"))
      (node (ref "R7") (pin "1") (pinfunction "1_1") (pintype "passive"))
      (node (ref "S3") (pin "1") (pinfunction "O_1") (pintype "passive"))
      (node (ref "TM1") (pin "1") (pinfunction "A_1") (pintype "passive"))
      (node (ref "TM2") (pin "1") (pinfunction "A_1") (pintype "passive"))
      (node (ref "U$1") (pin "12") (pinfunction "VSS_12") (pintype "power_in"))
      (node (ref "U$1") (pin "15") (pinfunction "INHIBIT_15") (pintype "passive"))
      (node (ref "U$3") (pin "2") (pinfunction "GND_2") (pintype "passive"))
      (node (ref "U1") (pin "9") (pinfunction "GND_9") (pintype "passive"))
      (node (ref "U10") (pin "1") (pinfunction "1_1") (pintype "passive"))
      (node (ref "U11") (pin "2") (pinfunction "SWITCHEMITTER_2") (pintype "passive"))
      (node (ref "U11") (pin "4") (pinfunction "GND_4") (pintype "power_in"))
      (node (ref "U11") (pin "9") (pinfunction "EPAD_9") (pintype "power_in"))
      (node (ref "U2") (pin "9") (pinfunction "GND_9") (pintype "passive"))
      (node (ref "U3") (pin "2") (pinfunction "COMMON_2") (pintype "power_in"))
      (node (ref "U3") (pin "4") (pinfunction "EPAD_4") (pintype "passive"))
      (node (ref "U4") (pin "21") (pinfunction "GND_21") (pintype "power_in"))
      (node (ref "U4") (pin "EPAD") (pinfunction "EPAD_EPAD") (pintype "passive"))
      (node (ref "U5") (pin "21") (pinfunction "GND_21") (pintype "power_in"))
      (node (ref "U5") (pin "EPAD") (pinfunction "EPAD_EPAD") (pintype "passive"))
      (node (ref "U6") (pin "GND") (pinfunction "GND_GND") (pintype "bidirectional"))
      (node (ref "U7") (pin "21") (pinfunction "AGND_21") (pintype "bidirectional"))
      (node (ref "U7") (pin "3") (pinfunction "GND_3") (pintype "bidirectional"))
      (node (ref "U7") (pin "5") (pinfunction "GND_5") (pintype "bidirectional"))
      (node (ref "U9") (pin "1") (pinfunction "1_1") (pintype "passive"))
      (node (ref "Y1") (pin "2") (pinfunction "2_2") (pintype "passive"))
    )
    (net (code "36") (name "MEGARX") (class "Default")
      (node (ref "Q2") (pin "3") (pinfunction "D_3") (pintype "passive"))
      (node (ref "R26") (pin "1") (pinfunction "1_1") (pintype "passive"))
      (node (ref "U7") (pin "30") (pinfunction "PD0(RXD)_30") (pintype "bidirectional"))
    )
    (net (code "37") (name "MEGARXLV") (class "Default")
      (node (ref "JP1") (pin "3") (pinfunction "3_3") (pintype "passive"))
      (node (ref "JP2") (pin "1") (pinfunction "1_1") (pintype "passive"))
      (node (ref "Q2") (pin "2") (pinfunction "S_2") (pintype "passive"))
      (node (ref "R27") (pin "1") (pinfunction "1_1") (pintype "passive"))
    )
    (net (code "38") (name "MEGATX") (class "Default")
      (node (ref "Q1") (pin "3") (pinfunction "D_3") (pintype "passive"))
      (node (ref "R23") (pin "1") (pinfunction "1_1") (pintype "passive"))
      (node (ref "U7") (pin "31") (pinfunction "PD1(TXD)_31") (pintype "bidirectional"))
    )
    (net (code "39") (name "MEGATXLV") (class "Default")
      (node (ref "JP1") (pin "1") (pinfunction "1_1") (pintype "passive"))
      (node (ref "JP2") (pin "3") (pinfunction "3_3") (pintype "passive"))
      (node (ref "Q1") (pin "2") (pinfunction "S_2") (pintype "passive"))
      (node (ref "R22") (pin "1") (pinfunction "1_1") (pintype "passive"))
    )
    (net (code "40") (name "Net-(20V!-Pad1)") (class "Default")
      (node (ref "20V!") (pin "1") (pinfunction "1_1") (pintype "passive"))
      (node (ref "C17") (pin "+") (pinfunction "+_+") (pintype "passive"))
      (node (ref "D2") (pin "C") (pinfunction "C_C") (pintype "passive"))
      (node (ref "R36") (pin "1") (pinfunction "1_1") (pintype "passive"))
    )
    (net (code "41") (name "Net-(D1-BLU)") (class "Default")
      (node (ref "D1") (pin "B") (pinfunction "BLU_B") (pintype "bidirectional"))
      (node (ref "R29") (pin "1") (pinfunction "1_1") (pintype "passive"))
    )
    (net (code "42") (name "Net-(D1-GRN)") (class "Default")
      (node (ref "D1") (pin "G") (pinfunction "GRN_G") (pintype "bidirectional"))
      (node (ref "R32") (pin "1") (pinfunction "1_1") (pintype "passive"))
    )
    (net (code "43") (name "Net-(D1-RED)") (class "Default")
      (node (ref "D1") (pin "R") (pinfunction "RED_R") (pintype "bidirectional"))
      (node (ref "R28") (pin "1") (pinfunction "1_1") (pintype "passive"))
    )
    (net (code "44") (name "Net-(L1-1)") (class "Default")
      (node (ref "L1") (pin "P$1") (pinfunction "1_P$1") (pintype "passive"))
      (node (ref "R33") (pin "2") (pinfunction "2_2") (pintype "passive"))
      (node (ref "R35") (pin "1") (pinfunction "1_1") (pintype "passive"))
      (node (ref "U11") (pin "7") (pinfunction "IPK_7") (pintype "passive"))
    )
    (net (code "45") (name "Net-(L1-2)") (class "Default")
      (node (ref "D2") (pin "A") (pinfunction "A_A") (pintype "passive"))
      (node (ref "L1") (pin "P$2") (pinfunction "2_P$2") (pintype "passive"))
      (node (ref "U11") (pin "1") (pinfunction "SWITCHCOLLECTOR_1") (pintype "passive"))
    )
    (net (code "46") (name "Net-(LED1-PadC)") (class "Default")
      (node (ref "LED1") (pin "C") (pinfunction "C_C") (pintype "passive"))
      (node (ref "R20") (pin "2") (pinfunction "2_2") (pintype "passive"))
    )
    (net (code "47") (name "Net-(LED2-PadC)") (class "Default")
      (node (ref "LED2") (pin "C") (pinfunction "C_C") (pintype "passive"))
      (node (ref "R7") (pin "2") (pinfunction "2_2") (pintype "passive"))
    )
    (net (code "48") (name "Net-(LED3-PadC)") (class "Default")
      (node (ref "LED3") (pin "C") (pinfunction "C_C") (pintype "passive"))
      (node (ref "R11") (pin "2") (pinfunction "2_2") (pintype "passive"))
    )
    (net (code "49") (name "Net-(LED4-PadC)") (class "Default")
      (node (ref "LED4") (pin "C") (pinfunction "C_C") (pintype "passive"))
      (node (ref "R12") (pin "2") (pinfunction "2_2") (pintype "passive"))
    )
    (net (code "50") (name "Net-(LED5-PadA)") (class "Default")
      (node (ref "LED5") (pin "A") (pinfunction "A_A") (pintype "passive"))
      (node (ref "U6") (pin "GPIO4") (pinfunction "GPIO4_GPIO4") (pintype "bidirectional"))
    )
    (net (code "51") (name "Net-(LED5-PadC)") (class "Default")
      (node (ref "LED5") (pin "C") (pinfunction "C_C") (pintype "passive"))
      (node (ref "R21") (pin "2") (pinfunction "2_2") (pintype "passive"))
    )
    (net (code "52") (name "Net-(LED6-PadC)") (class "Default")
      (node (ref "LED6") (pin "C") (pinfunction "C_C") (pintype "passive"))
      (node (ref "R25") (pin "2") (pinfunction "2_2") (pintype "passive"))
    )
    (net (code "53") (name "Net-(R14-Pad2)") (class "Default")
      (node (ref "R14") (pin "2") (pinfunction "2_2") (pintype "passive"))
      (node (ref "U6") (pin "GPIO15") (pinfunction "GPIO15_GPIO15") (pintype "bidirectional"))
    )
    (net (code "54") (name "Net-(R30-Pad1)") (class "Default")
      (node (ref "R30") (pin "1") (pinfunction "1_1") (pintype "passive"))
      (node (ref "U6") (pin "CH_PD") (pinfunction "CH_PD_CH_PD") (pintype "bidirectional"))
    )
    (net (code "55") (name "Net-(U$1-CHANNELIN{slash}OUT0)") (class "Default")
      (node (ref "U$1") (pin "9") (pinfunction "CHANNELIN/OUT0_9") (pintype "bidirectional"))
      (node (ref "U1") (pin "1") (pinfunction "1B_1") (pintype "passive"))
    )
    (net (code "56") (name "Net-(U$1-CHANNELIN{slash}OUT1)") (class "Default")
      (node (ref "U$1") (pin "8") (pinfunction "CHANNELIN/OUT1_8") (pintype "bidirectional"))
      (node (ref "U1") (pin "2") (pinfunction "2B_2") (pintype "passive"))
    )
    (net (code "57") (name "Net-(U$1-CHANNELIN{slash}OUT2)") (class "Default")
      (node (ref "U$1") (pin "7") (pinfunction "CHANNELIN/OUT2_7") (pintype "bidirectional"))
      (node (ref "U1") (pin "3") (pinfunction "3B_3") (pintype "passive"))
    )
    (net (code "58") (name "Net-(U$1-CHANNELIN{slash}OUT3)") (class "Default")
      (node (ref "U$1") (pin "6") (pinfunction "CHANNELIN/OUT3_6") (pintype "bidirectional"))
      (node (ref "U1") (pin "4") (pinfunction "4B_4") (pintype "passive"))
    )
    (net (code "59") (name "Net-(U$1-CHANNELIN{slash}OUT4)") (class "Default")
      (node (ref "U$1") (pin "5") (pinfunction "CHANNELIN/OUT4_5") (pintype "bidirectional"))
      (node (ref "U1") (pin "5") (pinfunction "5B_5") (pintype "passive"))
    )
    (net (code "60") (name "Net-(U$1-CHANNELIN{slash}OUT5)") (class "Default")
      (node (ref "U$1") (pin "4") (pinfunction "CHANNELIN/OUT5_4") (pintype "bidirectional"))
      (node (ref "U1") (pin "6") (pinfunction "6B_6") (pintype "passive"))
    )
    (net (code "61") (name "Net-(U$1-CHANNELIN{slash}OUT6)") (class "Default")
      (node (ref "U$1") (pin "3") (pinfunction "CHANNELIN/OUT6_3") (pintype "bidirectional"))
      (node (ref "U1") (pin "7") (pinfunction "7B_7") (pintype "passive"))
    )
    (net (code "62") (name "Net-(U$1-CHANNELIN{slash}OUT7)") (class "Default")
      (node (ref "U$1") (pin "2") (pinfunction "CHANNELIN/OUT7_2") (pintype "bidirectional"))
      (node (ref "U1") (pin "8") (pinfunction "8B_8") (pintype "passive"))
    )
    (net (code "63") (name "Net-(U$1-CHANNELIN{slash}OUT8)") (class "Default")
      (node (ref "U$1") (pin "23") (pinfunction "CHANNELIN/OUT8_23") (pintype "bidirectional"))
      (node (ref "U2") (pin "1") (pinfunction "1B_1") (pintype "passive"))
    )
    (net (code "64") (name "Net-(U$1-CHANNELIN{slash}OUT9)") (class "Default")
      (node (ref "U$1") (pin "22") (pinfunction "CHANNELIN/OUT9_22") (pintype "bidirectional"))
      (node (ref "U2") (pin "2") (pinfunction "2B_2") (pintype "passive"))
    )
    (net (code "65") (name "Net-(U$1-CHANNELIN{slash}OUT10)") (class "Default")
      (node (ref "U$1") (pin "21") (pinfunction "CHANNELIN/OUT10_21") (pintype "bidirectional"))
      (node (ref "U2") (pin "3") (pinfunction "3B_3") (pintype "passive"))
    )
    (net (code "66") (name "Net-(U$1-CHANNELIN{slash}OUT11)") (class "Default")
      (node (ref "U$1") (pin "20") (pinfunction "CHANNELIN/OUT11_20") (pintype "bidirectional"))
      (node (ref "U2") (pin "4") (pinfunction "4B_4") (pintype "passive"))
    )
    (net (code "67") (name "Net-(U$1-CHANNELIN{slash}OUT12)") (class "Default")
      (node (ref "U$1") (pin "19") (pinfunction "CHANNELIN/OUT12_19") (pintype "bidirectional"))
      (node (ref "U2") (pin "5") (pinfunction "5B_5") (pintype "passive"))
    )
    (net (code "68") (name "Net-(U$1-CHANNELIN{slash}OUT13)") (class "Default")
      (node (ref "U$1") (pin "18") (pinfunction "CHANNELIN/OUT13_18") (pintype "bidirectional"))
      (node (ref "U2") (pin "6") (pinfunction "6B_6") (pintype "passive"))
    )
    (net (code "69") (name "Net-(U$1-CHANNELIN{slash}OUT14)") (class "Default")
      (node (ref "U$1") (pin "17") (pinfunction "CHANNELIN/OUT14_17") (pintype "bidirectional"))
      (node (ref "U2") (pin "7") (pinfunction "7B_7") (pintype "passive"))
    )
    (net (code "70") (name "Net-(U$1-CHANNELIN{slash}OUT15)") (class "Default")
      (node (ref "U$1") (pin "16") (pinfunction "CHANNELIN/OUT15_16") (pintype "bidirectional"))
      (node (ref "U2") (pin "8") (pinfunction "8B_8") (pintype "passive"))
    )
    (net (code "71") (name "Net-(U$3-BYP)") (class "Default")
      (node (ref "C2") (pin "1") (pinfunction "1_1") (pintype "passive"))
      (node (ref "U$3") (pin "4") (pinfunction "BYP_4") (pintype "passive"))
    )
    (net (code "72") (name "Net-(U$3-~{SHDN})") (class "Default")
      (node (ref "R1") (pin "1") (pinfunction "1_1") (pintype "passive"))
      (node (ref "U$3") (pin "3") (pinfunction "~{SHDN}_3") (pintype "passive"))
    )
    (net (code "73") (name "Net-(U1-1C)") (class "Default")
      (node (ref "U1") (pin "18") (pinfunction "1C_18") (pintype "passive"))
      (node (ref "X1") (pin "8") (pinfunction "1_8") (pintype "passive"))
    )
    (net (code "74") (name "Net-(U1-2C)") (class "Default")
      (node (ref "U1") (pin "17") (pinfunction "2C_17") (pintype "passive"))
      (node (ref "X1") (pin "7") (pinfunction "1_7") (pintype "passive"))
    )
    (net (code "75") (name "Net-(U1-3C)") (class "Default")
      (node (ref "U1") (pin "16") (pinfunction "3C_16") (pintype "passive"))
      (node (ref "X1") (pin "4") (pinfunction "1_4") (pintype "passive"))
    )
    (net (code "76") (name "Net-(U1-4C)") (class "Default")
      (node (ref "U1") (pin "15") (pinfunction "4C_15") (pintype "passive"))
      (node (ref "X1") (pin "5") (pinfunction "1_5") (pintype "passive"))
    )
    (net (code "77") (name "Net-(U1-5C)") (class "Default")
      (node (ref "U1") (pin "14") (pinfunction "5C_14") (pintype "passive"))
      (node (ref "X1") (pin "6") (pinfunction "1_6") (pintype "passive"))
    )
    (net (code "78") (name "Net-(U1-6C)") (class "Default")
      (node (ref "U1") (pin "13") (pinfunction "6C_13") (pintype "passive"))
      (node (ref "X1") (pin "13") (pinfunction "1_13") (pintype "passive"))
    )
    (net (code "79") (name "Net-(U1-7C)") (class "Default")
      (node (ref "U1") (pin "12") (pinfunction "7C_12") (pintype "passive"))
      (node (ref "X1") (pin "14") (pinfunction "1_14") (pintype "passive"))
    )
    (net (code "80") (name "Net-(U1-8C)") (class "Default")
      (node (ref "U1") (pin "11") (pinfunction "8C_11") (pintype "passive"))
      (node (ref "X1") (pin "15") (pinfunction "1_15") (pintype "passive"))
    )
    (net (code "81") (name "Net-(U2-1C)") (class "Default")
      (node (ref "U2") (pin "18") (pinfunction "1C_18") (pintype "passive"))
      (node (ref "X1") (pin "12") (pinfunction "1_12") (pintype "passive"))
    )
    (net (code "82") (name "Net-(U2-2C)") (class "Default")
      (node (ref "U2") (pin "17") (pinfunction "2C_17") (pintype "passive"))
      (node (ref "X1") (pin "11") (pinfunction "1_11") (pintype "passive"))
    )
    (net (code "83") (name "Net-(U2-3C)") (class "Default")
      (node (ref "U2") (pin "16") (pinfunction "3C_16") (pintype "passive"))
      (node (ref "X1") (pin "10") (pinfunction "1_10") (pintype "passive"))
    )
    (net (code "84") (name "Net-(U2-4C)") (class "Default")
      (node (ref "U2") (pin "15") (pinfunction "4C_15") (pintype "passive"))
      (node (ref "X1") (pin "9") (pinfunction "1_9") (pintype "passive"))
    )
    (net (code "85") (name "Net-(U4-ADECAY)") (class "Default")
      (node (ref "R10") (pin "1") (pinfunction "1_1") (pintype "passive"))
      (node (ref "U4") (pin "3") (pinfunction "ADECAY_3") (pintype "input"))
    )
    (net (code "86") (name "Net-(U4-AISEN)") (class "Default")
      (node (ref "R16") (pin "1") (pinfunction "1_1") (pintype "passive"))
      (node (ref "U4") (pin "5") (pinfunction "AISEN_5") (pintype "bidirectional"))
    )
    (net (code "87") (name "Net-(U4-AOUT1)") (class "Default")
      (node (ref "J3") (pin "4") (pinfunction "4_4") (pintype "passive"))
      (node (ref "J4") (pin "4") (pinfunction "4_4") (pintype "passive"))
      (node (ref "U4") (pin "4") (pinfunction "AOUT1_4") (pintype "output"))
    )
    (net (code "88") (name "Net-(U4-AOUT2)") (class "Default")
      (node (ref "J3") (pin "3") (pinfunction "3_3") (pintype "passive"))
      (node (ref "J4") (pin "3") (pinfunction "3_3") (pintype "passive"))
      (node (ref "U4") (pin "6") (pinfunction "AOUT2_6") (pintype "output"))
    )
    (net (code "89") (name "Net-(U4-BDECAY)") (class "Default")
      (node (ref "R17") (pin "1") (pinfunction "1_1") (pintype "passive"))
      (node (ref "U4") (pin "2") (pinfunction "BDECAY_2") (pintype "input"))
    )
    (net (code "90") (name "Net-(U4-BISEN)") (class "Default")
      (node (ref "R15") (pin "1") (pinfunction "1_1") (pintype "passive"))
      (node (ref "U4") (pin "8") (pinfunction "BISEN_8") (pintype "bidirectional"))
    )
    (net (code "91") (name "Net-(U4-BOUT1)") (class "Default")
      (node (ref "J3") (pin "2") (pinfunction "2_2") (pintype "passive"))
      (node (ref "J4") (pin "1") (pinfunction "1_1") (pintype "passive"))
      (node (ref "U4") (pin "9") (pinfunction "BOUT1_9") (pintype "output"))
    )
    (net (code "92") (name "Net-(U4-BOUT2)") (class "Default")
      (node (ref "J3") (pin "1") (pinfunction "1_1") (pintype "passive"))
      (node (ref "J4") (pin "2") (pinfunction "2_2") (pintype "passive"))
      (node (ref "U4") (pin "7") (pinfunction "BOUT2_7") (pintype "output"))
    )
    (net (code "93") (name "Net-(U4-M0{slash}APHASE)") (class "Default")
      (node (ref "M02") (pin "1") (pinfunction "1_1") (pintype "passive"))
      (node (ref "U4") (pin "13") (pinfunction "M0/APHASE_13") (pintype "input"))
    )
    (net (code "94") (name "Net-(U4-M1)") (class "Default")
      (node (ref "M12") (pin "1") (pinfunction "1_1") (pintype "passive"))
      (node (ref "U4") (pin "14") (pinfunction "M1_14") (pintype "input"))
    )
    (net (code "95") (name "Net-(U4-NFAULT)") (class "Default")
      (node (ref "R18") (pin "1") (pinfunction "1_1") (pintype "passive"))
      (node (ref "U4") (pin "16") (pinfunction "NFAULT_16") (pintype "output"))
    )
    (net (code "96") (name "Net-(U4-NSLEEP)") (class "Default")
      (node (ref "R19") (pin "1") (pinfunction "1_1") (pintype "passive"))
      (node (ref "U4") (pin "1") (pinfunction "NSLEEP_1") (pintype "input"))
    )
    (net (code "97") (name "Net-(U4-VCP)") (class "Default")
      (node (ref "C9") (pin "1") (pinfunction "1_1") (pintype "passive"))
      (node (ref "U4") (pin "17") (pinfunction "VCP_17") (pintype "output"))
    )
    (net (code "98") (name "Net-(U5-ADECAY)") (class "Default")
      (node (ref "R2") (pin "1") (pinfunction "1_1") (pintype "passive"))
      (node (ref "U5") (pin "3") (pinfunction "ADECAY_3") (pintype "input"))
    )
    (net (code "99") (name "Net-(U5-AISEN)") (class "Default")
      (node (ref "R4") (pin "1") (pinfunction "1_1") (pintype "passive"))
      (node (ref "U5") (pin "5") (pinfunction "AISEN_5") (pintype "bidirectional"))
    )
    (net (code "100") (name "Net-(U5-AOUT1)") (class "Default")
      (node (ref "J2") (pin "4") (pinfunction "4_4") (pintype "passive"))
      (node (ref "J5") (pin "4") (pinfunction "4_4") (pintype "passive"))
      (node (ref "U5") (pin "4") (pinfunction "AOUT1_4") (pintype "output"))
    )
    (net (code "101") (name "Net-(U5-AOUT2)") (class "Default")
      (node (ref "J2") (pin "3") (pinfunction "3_3") (pintype "passive"))
      (node (ref "J5") (pin "3") (pinfunction "3_3") (pintype "passive"))
      (node (ref "U5") (pin "6") (pinfunction "AOUT2_6") (pintype "output"))
    )
    (net (code "102") (name "Net-(U5-BDECAY)") (class "Default")
      (node (ref "R5") (pin "1") (pinfunction "1_1") (pintype "passive"))
      (node (ref "U5") (pin "2") (pinfunction "BDECAY_2") (pintype "input"))
    )
    (net (code "103") (name "Net-(U5-BISEN)") (class "Default")
      (node (ref "R3") (pin "1") (pinfunction "1_1") (pintype "passive"))
      (node (ref "U5") (pin "8") (pinfunction "BISEN_8") (pintype "bidirectional"))
    )
    (net (code "104") (name "Net-(U5-BOUT1)") (class "Default")
      (node (ref "J2") (pin "2") (pinfunction "2_2") (pintype "passive"))
      (node (ref "J5") (pin "1") (pinfunction "1_1") (pintype "passive"))
      (node (ref "U5") (pin "9") (pinfunction "BOUT1_9") (pintype "output"))
    )
    (net (code "105") (name "Net-(U5-BOUT2)") (class "Default")
      (node (ref "J2") (pin "1") (pinfunction "1_1") (pintype "passive"))
      (node (ref "J5") (pin "2") (pinfunction "2_2") (pintype "passive"))
      (node (ref "U5") (pin "7") (pinfunction "BOUT2_7") (pintype "output"))
    )
    (net (code "106") (name "Net-(U5-M0{slash}APHASE)") (class "Default")
      (node (ref "M01") (pin "1") (pinfunction "1_1") (pintype "passive"))
      (node (ref "U5") (pin "13") (pinfunction "M0/APHASE_13") (pintype "input"))
    )
    (net (code "107") (name "Net-(U5-M1)") (class "Default")
      (node (ref "M11") (pin "1") (pinfunction "1_1") (pintype "passive"))
      (node (ref "U5") (pin "14") (pinfunction "M1_14") (pintype "input"))
    )
    (net (code "108") (name "Net-(U5-NFAULT)") (class "Default")
      (node (ref "R8") (pin "1") (pinfunction "1_1") (pintype "passive"))
      (node (ref "U5") (pin "16") (pinfunction "NFAULT_16") (pintype "output"))
    )
    (net (code "109") (name "Net-(U5-NSLEEP)") (class "Default")
      (node (ref "R9") (pin "1") (pinfunction "1_1") (pintype "passive"))
      (node (ref "U5") (pin "1") (pinfunction "NSLEEP_1") (pintype "input"))
    )
    (net (code "110") (name "Net-(U5-VCP)") (class "Default")
      (node (ref "C11") (pin "1") (pinfunction "1_1") (pintype "passive"))
      (node (ref "U5") (pin "17") (pinfunction "VCP_17") (pintype "output"))
    )
    (net (code "111") (name "Net-(U7-PB6(XTAL1{slash}TOSC1))") (class "Default")
      (node (ref "U7") (pin "7") (pinfunction "PB6(XTAL1/TOSC1)_7") (pintype "bidirectional"))
      (node (ref "Y1") (pin "1") (pinfunction "1_1") (pintype "passive"))
    )
    (net (code "112") (name "Net-(U7-PB7(XTAL2{slash}TOSC2))") (class "Default")
      (node (ref "U7") (pin "8") (pinfunction "PB7(XTAL2/TOSC2)_8") (pintype "bidirectional"))
      (node (ref "Y1") (pin "3") (pinfunction "3_3") (pintype "passive"))
    )
    (net (code "113") (name "Net-(U7-PD7(AIN1))") (class "Default")
      (node (ref "LED6") (pin "A") (pinfunction "A_A") (pintype "passive"))
      (node (ref "U7") (pin "11") (pinfunction "PD7(AIN1)_11") (pintype "bidirectional"))
    )
    (net (code "114") (name "Net-(U11-COMPARATORINVERTINGINPUT)") (class "Default")
      (node (ref "R34") (pin "2") (pinfunction "2_2") (pintype "passive"))
      (node (ref "R36") (pin "2") (pinfunction "2_2") (pintype "passive"))
      (node (ref "U11") (pin "5") (pinfunction "COMPARATORINVERTINGINPUT_5") (pintype "passive"))
    )
    (net (code "115") (name "Net-(U11-DRIVERCOLLECTOR)") (class "Default")
      (node (ref "R33") (pin "1") (pinfunction "1_1") (pintype "passive"))
      (node (ref "U11") (pin "8") (pinfunction "DRIVERCOLLECTOR_8") (pintype "passive"))
    )
    (net (code "116") (name "Net-(U11-TIMINGCAPACITOR)") (class "Default")
      (node (ref "C25") (pin "2") (pinfunction "2_2") (pintype "passive"))
      (node (ref "U11") (pin "3") (pinfunction "TIMINGCAPACITOR_3") (pintype "passive"))
    )
    (net (code "117") (name "REF1") (class "Default")
      (node (ref "TM1") (pin "2") (pinfunction "S_2") (pintype "passive"))
      (node (ref "U4") (pin "22") (pinfunction "AVREF_22") (pintype "input"))
      (node (ref "U4") (pin "23") (pinfunction "BVREF_23") (pintype "input"))
    )
    (net (code "118") (name "REF2") (class "Default")
      (node (ref "TM2") (pin "2") (pinfunction "S_2") (pintype "passive"))
      (node (ref "U5") (pin "22") (pinfunction "AVREF_22") (pintype "input"))
      (node (ref "U5") (pin "23") (pinfunction "BVREF_23") (pintype "input"))
    )
    (net (code "119") (name "VCC") (class "Default")
      (node (ref "C20") (pin "+") (pinfunction "+_+") (pintype "passive"))
      (node (ref "C21") (pin "1") (pinfunction "1_1") (pintype "passive"))
      (node (ref "C22") (pin "1") (pinfunction "1_1") (pintype "passive"))
      (node (ref "C23") (pin "1") (pinfunction "1_1") (pintype "passive"))
      (node (ref "C5") (pin "1") (pinfunction "1_1") (pintype "passive"))
      (node (ref "R35") (pin "2") (pinfunction "2_2") (pintype "passive"))
      (node (ref "U11") (pin "6") (pinfunction "VCC_6") (pintype "power_in"))
      (node (ref "U3") (pin "1") (pinfunction "INPUT_1") (pintype "input"))
      (node (ref "U4") (pin "18") (pinfunction "VM_18") (pintype "power_in"))
      (node (ref "U4") (pin "19") (pinfunction "VM_2_19") (pintype "power_in"))
      (node (ref "U5") (pin "18") (pinfunction "VM_18") (pintype "power_in"))
      (node (ref "U5") (pin "19") (pinfunction "VM_2_19") (pintype "power_in"))
      (node (ref "U8") (pin "1") (pinfunction "1_1") (pintype "passive"))
    )
    (net (code "120") (name "V_BATT") (class "Default")
      (node (ref "J6") (pin "4") (pinfunction "4_4") (pintype "passive"))
      (node (ref "U8") (pin "2") (pinfunction "2_2") (pintype "passive"))
    )
    (net (code "121") (name "unconnected-(J6-Pad2)") (class "Default")
      (node (ref "J6") (pin "2") (pinfunction "2_2") (pintype "passive"))
    )
    (net (code "122") (name "unconnected-(J6-Pad3)") (class "Default")
      (node (ref "J6") (pin "3") (pinfunction "3_3") (pintype "passive"))
    )
    (net (code "123") (name "unconnected-(J10-Pad2)") (class "Default")
      (node (ref "J10") (pin "2") (pinfunction "2_2") (pintype "passive"))
    )
    (net (code "124") (name "unconnected-(U2-5C-Pad14)") (class "Default")
      (node (ref "U2") (pin "14") (pinfunction "5C_14") (pintype "passive"))
    )
    (net (code "125") (name "unconnected-(U2-6C-Pad13)") (class "Default")
      (node (ref "U2") (pin "13") (pinfunction "6C_13") (pintype "passive"))
    )
    (net (code "126") (name "unconnected-(U2-7C-Pad12)") (class "Default")
      (node (ref "U2") (pin "12") (pinfunction "7C_12") (pintype "passive"))
    )
    (net (code "127") (name "unconnected-(U2-8C-Pad11)") (class "Default")
      (node (ref "U2") (pin "11") (pinfunction "8C_11") (pintype "passive"))
    )
    (net (code "128") (name "unconnected-(U6-*GPIO9-PadGPIO9)") (class "Default")
      (node (ref "U6") (pin "GPIO9") (pinfunction "*GPIO9_GPIO9") (pintype "bidirectional"))
    )
    (net (code "129") (name "unconnected-(U6-*GPIO10-PadGPIO10)") (class "Default")
      (node (ref "U6") (pin "GPIO10") (pinfunction "*GPIO10_GPIO10") (pintype "bidirectional"))
    )
    (net (code "130") (name "unconnected-(U6-PadADC)") (class "Default")
      (node (ref "U6") (pin "ADC") (pinfunction "ADC_ADC") (pintype "bidirectional"))
    )
    (net (code "131") (name "unconnected-(U6-PadCS0)") (class "Default")
      (node (ref "U6") (pin "CS0") (pinfunction "CS0_CS0") (pintype "bidirectional"))
    )
    (net (code "132") (name "unconnected-(U6-PadGPIO5)") (class "Default")
      (node (ref "U6") (pin "GPIO5") (pinfunction "GPIO5_GPIO5") (pintype "bidirectional"))
    )
    (net (code "133") (name "unconnected-(U6-PadMISO)") (class "Default")
      (node (ref "U6") (pin "MISO") (pinfunction "MISO_MISO") (pintype "bidirectional"))
    )
    (net (code "134") (name "unconnected-(U6-PadMOSI)") (class "Default")
      (node (ref "U6") (pin "MOSI") (pinfunction "MOSI_MOSI") (pintype "bidirectional"))
    )
    (net (code "135") (name "unconnected-(U6-PadSCLK)") (class "Default")
      (node (ref "U6") (pin "SCLK") (pinfunction "SCLK_SCLK") (pintype "bidirectional"))
    )
    (net (code "136") (name "unconnected-(U7-ADC6-Pad19)") (class "Default")
      (node (ref "U7") (pin "19") (pinfunction "ADC6_19") (pintype "bidirectional"))
    )
    (net (code "137") (name "unconnected-(U7-ADC7-Pad22)") (class "Default")
      (node (ref "U7") (pin "22") (pinfunction "ADC7_22") (pintype "bidirectional"))
    )
    (net (code "138") (name "unconnected-(U7-AREF-Pad20)") (class "Default")
      (node (ref "U7") (pin "20") (pinfunction "AREF_20") (pintype "bidirectional"))
    )
    (net (code "139") (name "unconnected-(U7-PC4(ADC4{slash}SDA)-Pad27)") (class "Default")
      (node (ref "U7") (pin "27") (pinfunction "PC4(ADC4/SDA)_27") (pintype "bidirectional"))
    )
    (net (code "140") (name "unconnected-(U7-PC5(ADC5{slash}SCL)-Pad28)") (class "Default")
      (node (ref "U7") (pin "28") (pinfunction "PC5(ADC5/SCL)_28") (pintype "bidirectional"))
    )
    (net (code "141") (name "unconnected-(U8-Pad3)") (class "Default")
      (node (ref "U8") (pin "3") (pinfunction "3_3") (pintype "passive"))
    )
    (net (code "142") (name "unconnected-(X1-Pad1)") (class "Default")
      (node (ref "X1") (pin "1") (pinfunction "1_1") (pintype "passive"))
    )
    (net (code "143") (name "unconnected-(X1I-1-Pad2)") (class "Default")
      (node (ref "X1") (pin "2") (pinfunction "1_2") (pintype "passive"))
    )
  )
)
